# SDcard.net
KiCad netlist of a schematic drawn in Altium Designer
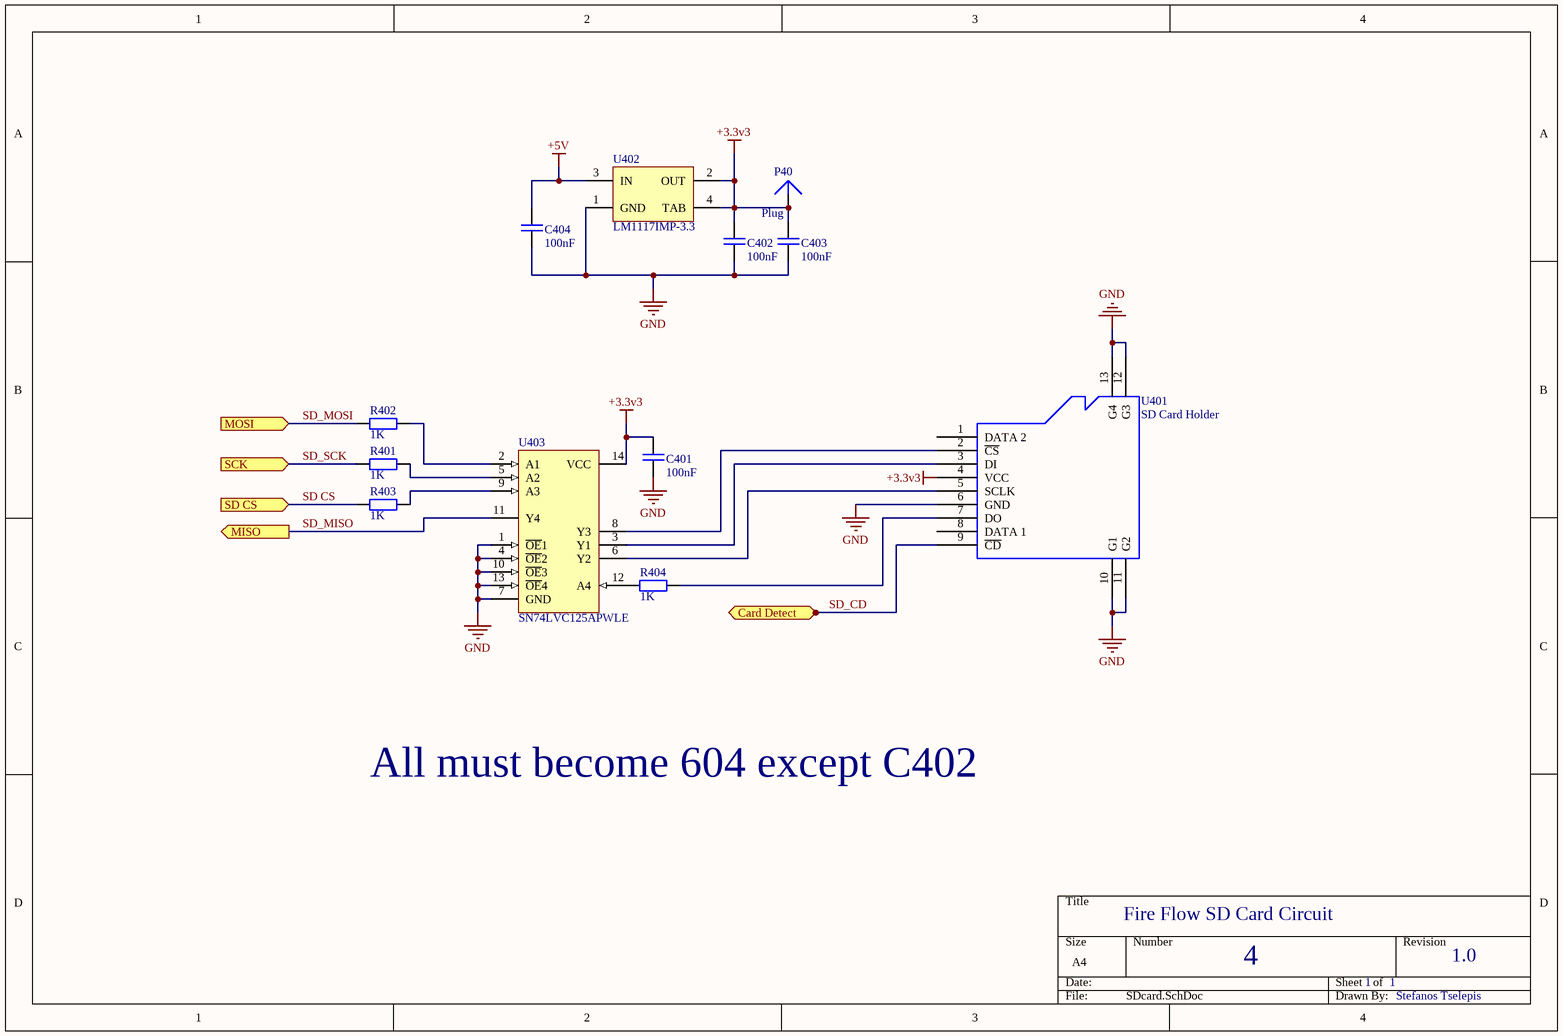
[diagram p0: SDcard.SchDoc]

(export (version "E")
  (design (tool "Eeschema 10.0.6"))
  (components
    (comp (ref "C401")
      (value "100nF")
      (footprint "CC2013-0805")
      (libsource (lib "FireFlow Lib") (part "Cap Metal Film"))
    )
    (comp (ref "C402")
      (value "100nF")
      (footprint "CC2013-0805")
      (libsource (lib "FireFlow Lib") (part "Cap Metal Film"))
    )
    (comp (ref "C403")
      (value "100nF")
      (footprint "CC2013-0805")
      (libsource (lib "FireFlow Lib") (part "Cap Metal Film"))
    )
    (comp (ref "C404")
      (value "100nF")
      (footprint "CC2013-0805")
      (libsource (lib "FireFlow Lib") (part "Cap Metal Film"))
    )
    (comp (ref "P40")
      (value "Plug")
      (footprint "PIN1")
      (fields (field (name "PUBLISHER") "Altium Limited"))
      (libsource (lib "FireFlow Lib") (part "Plug"))
    )
    (comp (ref "R401") (value "1K") (footprint "CR2012-0805") (libsource (lib "") (part "Resistor_1")))
    (comp (ref "R402") (value "1K") (footprint "CR2012-0805") (libsource (lib "") (part "Resistor_1")))
    (comp (ref "R403") (value "1K") (footprint "CR2012-0805") (libsource (lib "") (part "Resistor_1")))
    (comp (ref "R404")
      (value "1K")
      (footprint "CR2012-0805")
      (libsource (lib "FireFlow Lib") (part "Resistor"))
    )
    (comp (ref "U401")
      (value "SD Card Holder")
      (footprint "Micro SD Card holder")
      (libsource (lib "FireFlow Lib") (part "SD Card Holder"))
    )
    (comp (ref "U402")
      (value "LM1117IMP-3.3")
      (footprint "MP04A_N")
      (description "800mA Low-Dropout Linear Regulator, 4-pin SOT-223")
      (fields
        (field (name "MANUFACTURER") "National Semiconductor")
        (field (name "PUBLISHER") "Altium Limited")
      )
      (libsource (lib "FireFlow Lib") (part "LM1117IMP-3.3"))
    )
    (comp (ref "U403")
      (value "SN74LVC125APWLE")
      (footprint "PW014_N")
      (description "Quadruple Bus Buffer Gate with 3-State Outputs")
      (libsource (lib "FireFlow Lib") (part "SN74LVC125APWLE"))
    )
  )
  (nets
    (net (code "1") (name "+3.3v3") (class "Default")
      (node (ref "C401") (pin "1") (pinfunction "1_1") (pintype "passive"))
      (node (ref "C402") (pin "1") (pinfunction "1_1") (pintype "passive"))
      (node (ref "C403") (pin "1") (pinfunction "1_1") (pintype "passive"))
      (node (ref "P40") (pin "1") (pinfunction "1_1") (pintype "passive"))
      (node (ref "U401") (pin "4") (pinfunction "VCC_4") (pintype "passive"))
      (node (ref "U402") (pin "2") (pinfunction "OUT_2") (pintype "power_in"))
      (node (ref "U402") (pin "4") (pinfunction "TAB_4") (pintype "power_in"))
      (node (ref "U403") (pin "14") (pinfunction "VCC_14") (pintype "power_in"))
    )
    (net (code "2") (name "+5V") (class "Default")
      (node (ref "C404") (pin "1") (pinfunction "1_1") (pintype "passive"))
      (node (ref "U402") (pin "3") (pinfunction "IN_3") (pintype "power_in"))
    )
    (net (code "3") (name "/SD CS") (class "Default")
      (node (ref "R403") (pin "2") (pinfunction "2_2") (pintype "passive"))
    )
    (net (code "4") (name "/SD_CD") (class "Default")
      (node (ref "U401") (pin "9") (pinfunction "~{CD}_9") (pintype "passive"))
    )
    (net (code "5") (name "/SD_MISO") (class "Default")
      (node (ref "U403") (pin "11") (pinfunction "Y4_11") (pintype "tri_state"))
    )
    (net (code "6") (name "/SD_MOSI") (class "Default")
      (node (ref "R402") (pin "2") (pinfunction "2_2") (pintype "passive"))
    )
    (net (code "7") (name "/SD_SCK") (class "Default")
      (node (ref "R401") (pin "2") (pinfunction "2_2") (pintype "passive"))
    )
    (net (code "8") (name "GND") (class "Default")
      (node (ref "C401") (pin "2") (pinfunction "2_2") (pintype "passive"))
      (node (ref "C402") (pin "2") (pinfunction "2_2") (pintype "passive"))
      (node (ref "C403") (pin "2") (pinfunction "2_2") (pintype "passive"))
      (node (ref "C404") (pin "2") (pinfunction "2_2") (pintype "passive"))
      (node (ref "U401") (pin "10") (pinfunction "G1_10") (pintype "passive"))
      (node (ref "U401") (pin "11") (pinfunction "G2_11") (pintype "passive"))
      (node (ref "U401") (pin "12") (pinfunction "G3_12") (pintype "passive"))
      (node (ref "U401") (pin "13") (pinfunction "G4_13") (pintype "passive"))
      (node (ref "U401") (pin "6") (pinfunction "GND_6") (pintype "passive"))
      (node (ref "U402") (pin "1") (pinfunction "GND_1") (pintype "power_in"))
      (node (ref "U403") (pin "1") (pinfunction "~{OE}1_1") (pintype "input"))
      (node (ref "U403") (pin "10") (pinfunction "~{OE}3_10") (pintype "input"))
      (node (ref "U403") (pin "13") (pinfunction "~{OE}4_13") (pintype "input"))
      (node (ref "U403") (pin "4") (pinfunction "~{OE}2_4") (pintype "input"))
      (node (ref "U403") (pin "7") (pinfunction "GND_7") (pintype "power_in"))
    )
    (net (code "9") (name "Net-(U401-DI)") (class "Default")
      (node (ref "U401") (pin "3") (pinfunction "DI_3") (pintype "passive"))
      (node (ref "U403") (pin "3") (pinfunction "Y1_3") (pintype "tri_state"))
    )
    (net (code "10") (name "Net-(U401-DO)") (class "Default")
      (node (ref "R404") (pin "2") (pinfunction "2_2") (pintype "passive"))
      (node (ref "U401") (pin "7") (pinfunction "DO_7") (pintype "passive"))
    )
    (net (code "11") (name "Net-(U401-SCLK)") (class "Default")
      (node (ref "U401") (pin "5") (pinfunction "SCLK_5") (pintype "passive"))
      (node (ref "U403") (pin "6") (pinfunction "Y2_6") (pintype "tri_state"))
    )
    (net (code "12") (name "Net-(U401-~{CS})") (class "Default")
      (node (ref "U401") (pin "2") (pinfunction "~{CS}_2") (pintype "passive"))
      (node (ref "U403") (pin "8") (pinfunction "Y3_8") (pintype "tri_state"))
    )
    (net (code "13") (name "Net-(U403-A1)") (class "Default")
      (node (ref "R402") (pin "1") (pinfunction "1_1") (pintype "passive"))
      (node (ref "U403") (pin "2") (pinfunction "A1_2") (pintype "input"))
    )
    (net (code "14") (name "Net-(U403-A2)") (class "Default")
      (node (ref "R401") (pin "1") (pinfunction "1_1") (pintype "passive"))
      (node (ref "U403") (pin "5") (pinfunction "A2_5") (pintype "input"))
    )
    (net (code "15") (name "Net-(U403-A3)") (class "Default")
      (node (ref "R403") (pin "1") (pinfunction "1_1") (pintype "passive"))
      (node (ref "U403") (pin "9") (pinfunction "A3_9") (pintype "input"))
    )
    (net (code "16") (name "Net-(U403-A4)") (class "Default")
      (node (ref "R404") (pin "1") (pinfunction "1_1") (pintype "passive"))
      (node (ref "U403") (pin "12") (pinfunction "A4_12") (pintype "input"))
    )
    (net (code "17") (name "unconnected-(U401-DATA_1-Pad8)") (class "Default")
      (node (ref "U401") (pin "8") (pinfunction "DATA_1_8") (pintype "passive"))
    )
    (net (code "18") (name "unconnected-(U401-DATA_2-Pad1)") (class "Default")
      (node (ref "U401") (pin "1") (pinfunction "DATA_2_1") (pintype "passive"))
    )
  )
)
